# VoltageRegulator3_3.net
KiCad netlist of a schematic drawn in Altium Designer
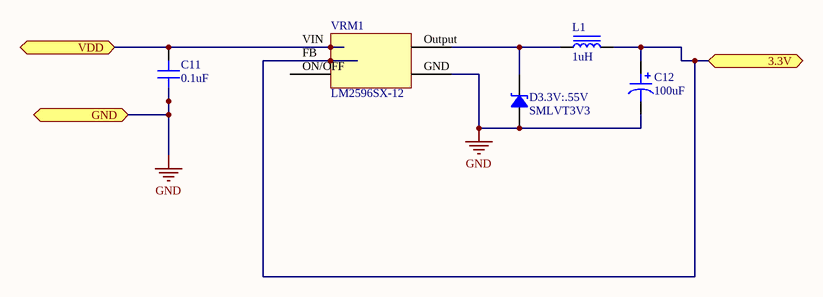
[diagram p0: VoltageRegulator3.3.schdoc]

(export (version "E")
  (design (tool "Eeschema 10.0.6"))
  (components
    (comp (ref "C11")
      (value "0.1uF")
      (footprint "CAP 0402/1005")
      (description "CAP CER 0.1UF 16V X7R 0402")
      (fields
        (field (name "PART NUMBER") "C1005X7R1C104K050BC")
        (field (name "MANUFACTURER") "TDK Corporation")
      )
      (libsource (lib "Celestial Library Database") (part "Capacitor"))
    )
    (comp (ref "C12")
      (value "100uF")
      (footprint "CAP ALUM 6.6MM")
      (description "CAP POLYMER 100UF 20% 16V SMD")
      (fields
        (field (name "PART NUMBER") "16SVPC100M")
        (field (name "MANUFACTURER") "Panasonic Electronic Components")
      )
      (libsource (lib "Celestial Library Database") (part "Polarised Capacitor"))
    )
    (comp (ref "D3.3V:.55V")
      (value "SMLVT3V3")
      (footprint "ST DO214AA SMB")
      (description "TVS DIODE 3.3VWM 10.3VC SMB")
      (fields (field (name "MANUFACTURER") "STMicroelectronics"))
      (libsource (lib "Celestial Library Database") (part "Diode Zener"))
    )
    (comp (ref "L1")
      (value "1uH")
      (footprint "TDK VLS252010CX")
      (description "FIXED IND 1UH 2.29A 65 MOHM SMD")
      (fields (field (name "PART NUMBER") "VLS252010CX-1R0M") (field (name "MANUFACTURER") "TDK Corporation"))
      (libsource (lib "Celestial Library Database") (part "Inductor"))
    )
    (comp (ref "VRM1")
      (value "LM2596SX-12")
      (footprint "DPAK170P1418X200-6L")
      (libsource (lib "Schlib2") (part "LM2596SX-12"))
    )
  )
  (nets
    (net (code "1") (name "/3.3V") (class "Default")
      (node (ref "C12") (pin "1") (pinfunction "1_1") (pintype "passive"))
      (node (ref "L1") (pin "2") (pinfunction "2_2") (pintype "passive"))
      (node (ref "VRM1") (pin "FB") (pinfunction "*_FB") (pintype "passive"))
    )
    (net (code "2") (name "/VDD") (class "Default")
      (node (ref "C11") (pin "2") (pinfunction "2_2") (pintype "passive"))
      (node (ref "VRM1") (pin "VIN") (pinfunction "Vin_VIN") (pintype "passive"))
    )
    (net (code "3") (name "GND") (class "Default")
      (node (ref "C11") (pin "1") (pinfunction "1_1") (pintype "passive"))
      (node (ref "C12") (pin "2") (pinfunction "2_2") (pintype "passive"))
      (node (ref "D3.3V:.55V") (pin "1") (pinfunction "1_1") (pintype "passive"))
      (node (ref "VRM1") (pin "GND") (pinfunction "*_GND") (pintype "passive"))
    )
    (net (code "4") (name "Net-(D3.3V:.55V-Pad2)") (class "Default")
      (node (ref "D3.3V:.55V") (pin "2") (pinfunction "2_2") (pintype "passive"))
      (node (ref "L1") (pin "1") (pinfunction "1_1") (pintype "passive"))
      (node (ref "VRM1") (pin "Output") (pinfunction "*_Output") (pintype "passive"))
    )
    (net (code "5") (name "unconnected-(VRM1-*-PadON{slash}OFF)") (class "Default")
      (node (ref "VRM1") (pin "ON/OFF") (pinfunction "*_ON/OFF") (pintype "passive"))
    )
  )
)
